# final.net
KiCad netlist of a schematic drawn in EAGLE
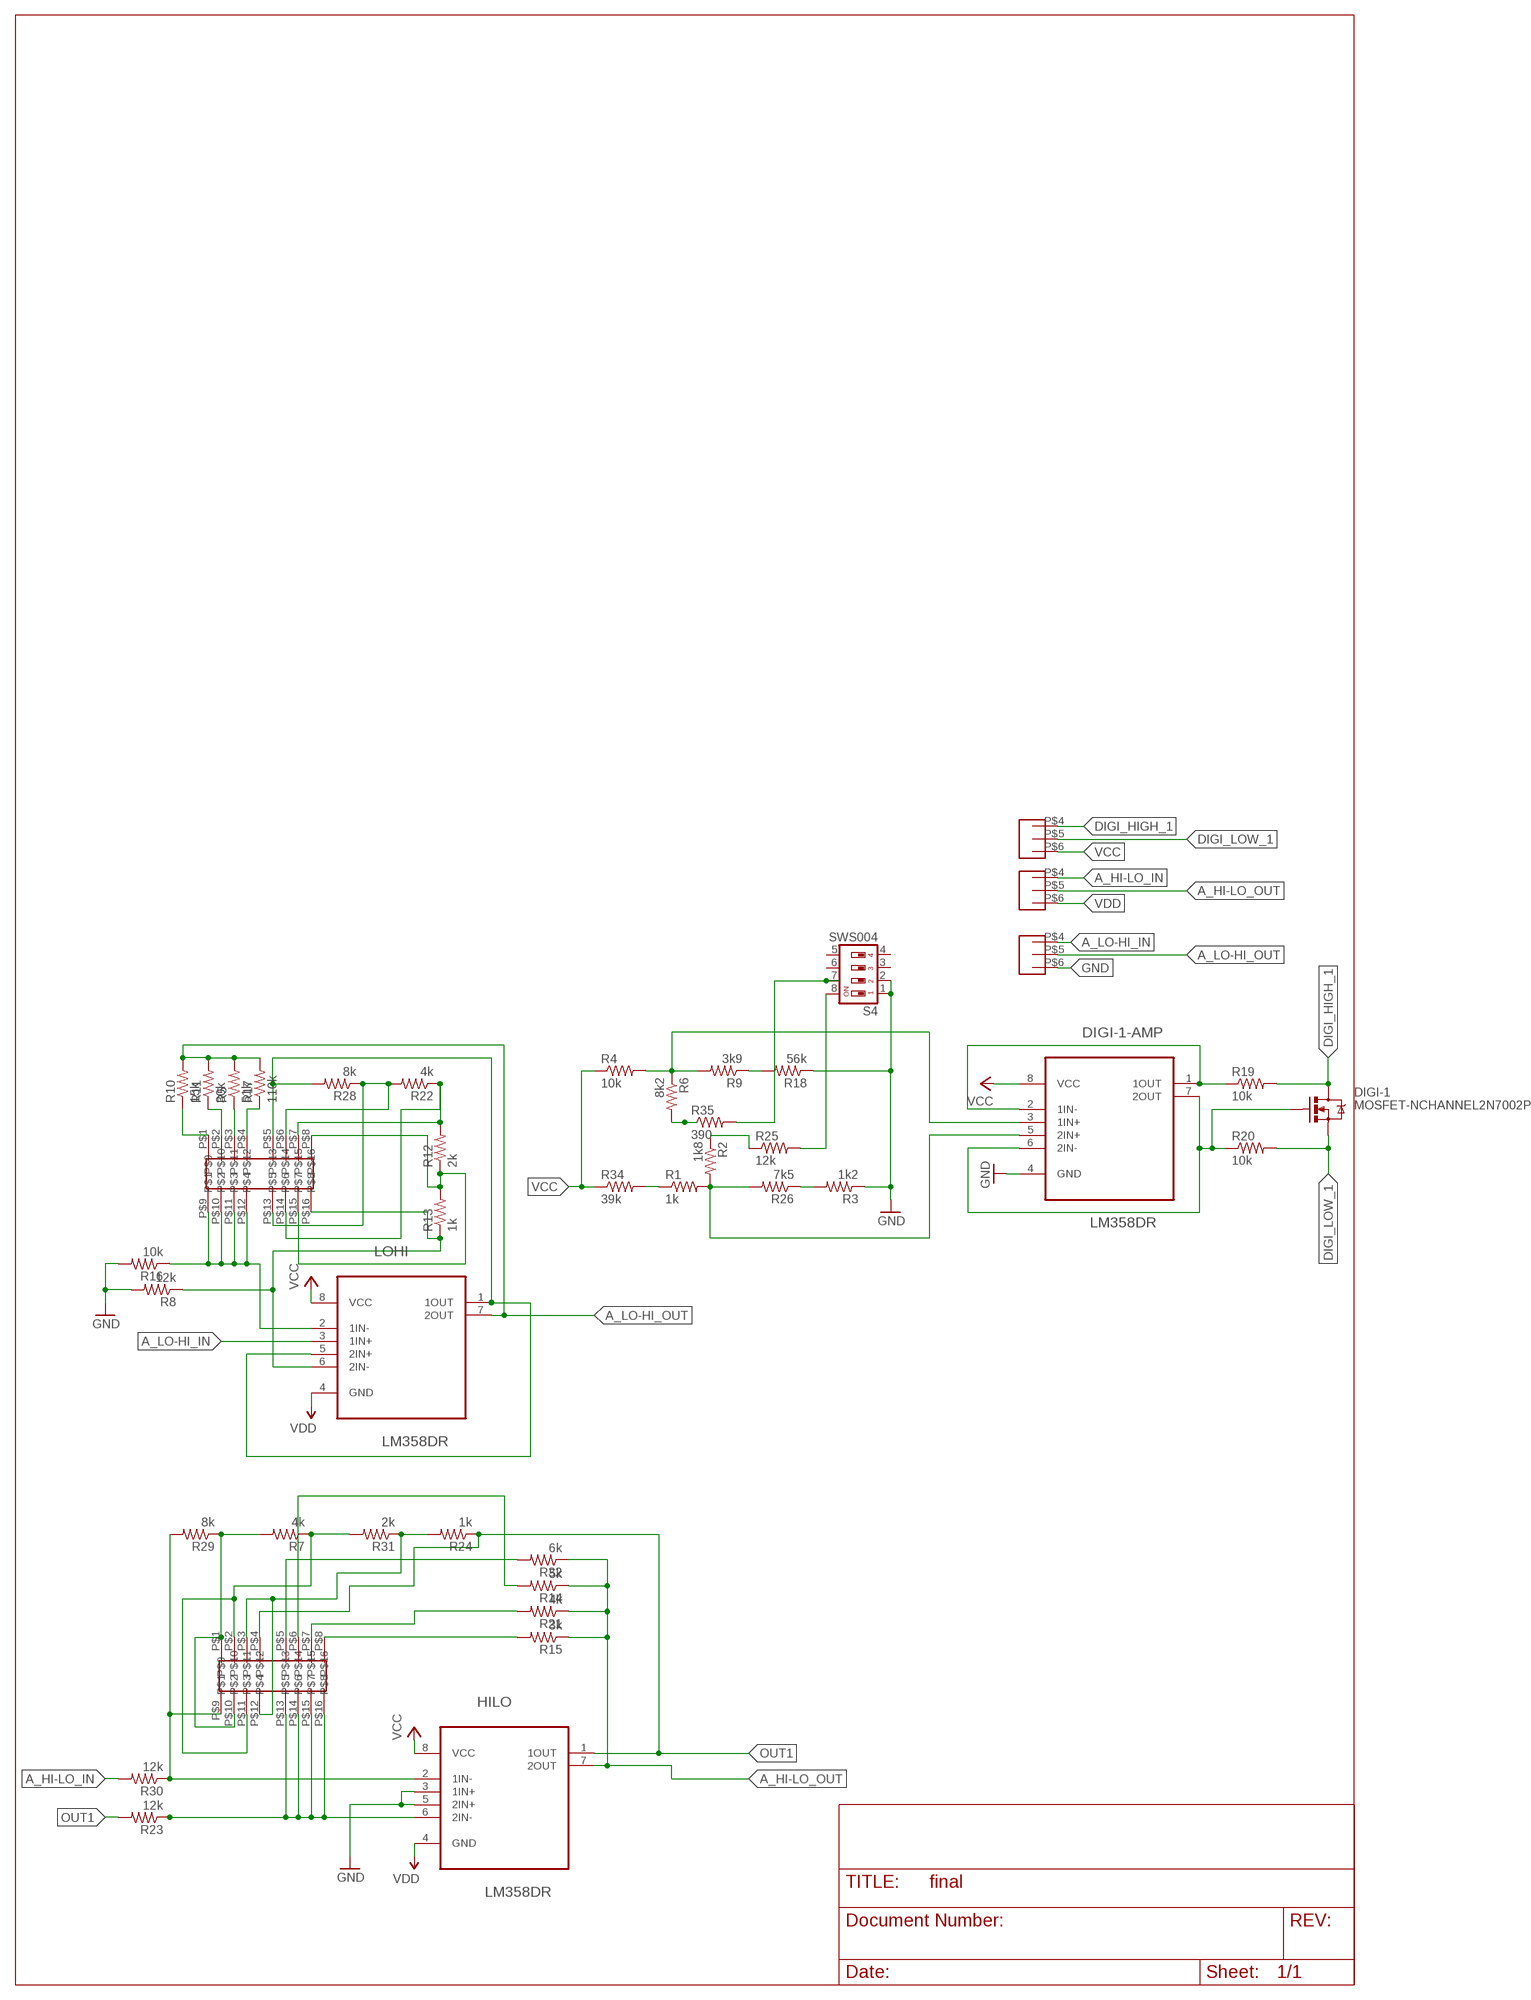
[diagram p0: schematic, sheet 1]

(export (version "E")
  (design (tool "Eeschema 10.0.6"))
  (components
    (comp (ref "DIGI-1")
      (value "MOSFET-NCHANNEL2N7002PW")
      (footprint "eagle-import:SOT323")
      (libsource (lib "eagle-import") (part "MOSFET-NCHANNEL2N7002PW"))
    )
    (comp (ref "DIGI-1-AMP")
      (value "LM358DR")
      (footprint "eagle-import:SOIC127P600X175-8N")
      (libsource (lib "eagle-import") (part "LM358DR"))
    )
    (comp (ref "HILO")
      (value "LM358DR")
      (footprint "eagle-import:SOIC127P600X175-8N")
      (libsource (lib "eagle-import") (part "LM358DR"))
    )
    (comp (ref "LOHI")
      (value "LM358DR")
      (footprint "eagle-import:SOIC127P600X175-8N")
      (libsource (lib "eagle-import") (part "LM358DR"))
    )
    (comp (ref "R1")
      (value "1k")
      (footprint "eagle-import:R0805")
      (libsource (lib "eagle-import") (part "R-US_R0805"))
    )
    (comp (ref "R2")
      (value "1k8")
      (footprint "eagle-import:R0805")
      (libsource (lib "eagle-import") (part "R-US_R0805"))
    )
    (comp (ref "R3")
      (value "1k2")
      (footprint "eagle-import:R0805")
      (libsource (lib "eagle-import") (part "R-US_R0805"))
    )
    (comp (ref "R4")
      (value "10k")
      (footprint "eagle-import:R0805")
      (libsource (lib "eagle-import") (part "R-US_R0805"))
    )
    (comp (ref "R5")
      (value "51k")
      (footprint "eagle-import:R0805")
      (libsource (lib "eagle-import") (part "R-US_R0805"))
    )
    (comp (ref "R6")
      (value "8k2")
      (footprint "eagle-import:R0805")
      (libsource (lib "eagle-import") (part "R-US_R0805"))
    )
    (comp (ref "R7")
      (value "4k")
      (footprint "eagle-import:0207_15")
      (libsource (lib "eagle-import") (part "R-US_0207/15"))
    )
    (comp (ref "R8")
      (value "12k")
      (footprint "eagle-import:R0805")
      (libsource (lib "eagle-import") (part "R-US_R0805"))
    )
    (comp (ref "R9")
      (value "3k9")
      (footprint "eagle-import:R0805")
      (libsource (lib "eagle-import") (part "R-US_R0805"))
    )
    (comp (ref "R10")
      (value "15k")
      (footprint "eagle-import:R0805")
      (libsource (lib "eagle-import") (part "R-US_R0805"))
    )
    (comp (ref "R11")
      (value "30k")
      (footprint "eagle-import:R0805")
      (libsource (lib "eagle-import") (part "R-US_R0805"))
    )
    (comp (ref "R12")
      (value "2k")
      (footprint "eagle-import:0207_15")
      (libsource (lib "eagle-import") (part "R-US_0207/15"))
    )
    (comp (ref "R13")
      (value "1k")
      (footprint "eagle-import:R0805")
      (libsource (lib "eagle-import") (part "R-US_R0805"))
    )
    (comp (ref "R14")
      (value "5k")
      (footprint "eagle-import:R0805")
      (libsource (lib "eagle-import") (part "R-US_R0805"))
    )
    (comp (ref "R15")
      (value "3k")
      (footprint "eagle-import:R0805")
      (libsource (lib "eagle-import") (part "R-US_R0805"))
    )
    (comp (ref "R16")
      (value "10k")
      (footprint "eagle-import:R0805")
      (libsource (lib "eagle-import") (part "R-US_R0805"))
    )
    (comp (ref "R17")
      (value "110k")
      (footprint "eagle-import:R0805")
      (libsource (lib "eagle-import") (part "R-US_R0805"))
    )
    (comp (ref "R18")
      (value "56k")
      (footprint "eagle-import:R0805")
      (libsource (lib "eagle-import") (part "R-US_R0805"))
    )
    (comp (ref "R19")
      (value "10k")
      (footprint "eagle-import:R0805")
      (libsource (lib "eagle-import") (part "R-US_R0805"))
    )
    (comp (ref "R20")
      (value "10k")
      (footprint "eagle-import:R0805")
      (libsource (lib "eagle-import") (part "R-US_R0805"))
    )
    (comp (ref "R21")
      (value "4k")
      (footprint "eagle-import:R0805")
      (libsource (lib "eagle-import") (part "R-US_R0805"))
    )
    (comp (ref "R22")
      (value "4k")
      (footprint "eagle-import:0207_15")
      (libsource (lib "eagle-import") (part "R-US_0207/15"))
    )
    (comp (ref "R23")
      (value "12k")
      (footprint "eagle-import:R0805")
      (libsource (lib "eagle-import") (part "R-US_R0805"))
    )
    (comp (ref "R24")
      (value "1k")
      (footprint "eagle-import:0207_15")
      (libsource (lib "eagle-import") (part "R-US_0207/15"))
    )
    (comp (ref "R25")
      (value "12k")
      (footprint "eagle-import:R0805")
      (libsource (lib "eagle-import") (part "R-US_R0805"))
    )
    (comp (ref "R26")
      (value "7k5")
      (footprint "eagle-import:R0805")
      (libsource (lib "eagle-import") (part "R-US_R0805"))
    )
    (comp (ref "R28")
      (value "8k")
      (footprint "eagle-import:0207_15")
      (libsource (lib "eagle-import") (part "R-US_0207/15"))
    )
    (comp (ref "R29")
      (value "8k")
      (footprint "eagle-import:R0805")
      (libsource (lib "eagle-import") (part "R-US_R0805"))
    )
    (comp (ref "R30")
      (value "12k")
      (footprint "eagle-import:R0805")
      (libsource (lib "eagle-import") (part "R-US_R0805"))
    )
    (comp (ref "R31")
      (value "2k")
      (footprint "eagle-import:0207_15")
      (libsource (lib "eagle-import") (part "R-US_0207/15"))
    )
    (comp (ref "R32")
      (value "6k")
      (footprint "eagle-import:R0805")
      (libsource (lib "eagle-import") (part "R-US_R0805"))
    )
    (comp (ref "R34")
      (value "39k")
      (footprint "eagle-import:R0805")
      (libsource (lib "eagle-import") (part "R-US_R0805"))
    )
    (comp (ref "R35")
      (value "390")
      (footprint "eagle-import:R0805")
      (libsource (lib "eagle-import") (part "R-US_R0805"))
    )
    (comp (ref "S4")
      (value "SWS004")
      (footprint "eagle-import:SMS-004")
      (libsource (lib "eagle-import") (part "SWS004"))
    )
    (comp (ref "U$2")
      (value "USCO_8PIN_SWITCH")
      (footprint "eagle-import:USCO_8PIN_SWITCH")
      (libsource (lib "eagle-import") (part "USCO_8PIN_SWITCH"))
    )
    (comp (ref "U$3")
      (value "USCO_8PIN_SWITCH")
      (footprint "eagle-import:USCO_8PIN_SWITCH")
      (libsource (lib "eagle-import") (part "USCO_8PIN_SWITCH"))
    )
    (comp (ref "U$4")
      (value "5.08PITCHTERMINAL")
      (footprint "eagle-import:10KPL508")
      (libsource (lib "eagle-import") (part "5.08PITCHTERMINAL"))
    )
    (comp (ref "U$5")
      (value "5.08PITCHTERMINAL")
      (footprint "eagle-import:10KPL508")
      (libsource (lib "eagle-import") (part "5.08PITCHTERMINAL"))
    )
    (comp (ref "U$6")
      (value "5.08PITCHTERMINAL")
      (footprint "eagle-import:10KPL508")
      (libsource (lib "eagle-import") (part "5.08PITCHTERMINAL"))
    )
  )
  (nets
    (net (code "1") (name "A_HI-LO_IN") (class "Default")
      (node (ref "R30") (pin "2") (pinfunction "2_2") (pintype "passive"))
      (node (ref "U$4") (pin "P$4") (pinfunction "P$4_P$4") (pintype "bidirectional"))
    )
    (net (code "2") (name "A_HI-LO_OUT") (class "Default")
      (node (ref "HILO") (pin "7") (pinfunction "2OUT_7") (pintype "output"))
      (node (ref "R14") (pin "1") (pinfunction "1_1") (pintype "passive"))
      (node (ref "R15") (pin "1") (pinfunction "1_1") (pintype "passive"))
      (node (ref "R21") (pin "1") (pinfunction "1_1") (pintype "passive"))
      (node (ref "R32") (pin "1") (pinfunction "1_1") (pintype "passive"))
      (node (ref "U$4") (pin "P$5") (pinfunction "P$5_P$5") (pintype "bidirectional"))
    )
    (net (code "3") (name "A_LO-HI_IN") (class "Default")
      (node (ref "LOHI") (pin "3") (pinfunction "1IN+_3") (pintype "input"))
      (node (ref "U$6") (pin "P$4") (pinfunction "P$4_P$4") (pintype "bidirectional"))
    )
    (net (code "4") (name "A_LO-HI_OUT") (class "Default")
      (node (ref "LOHI") (pin "7") (pinfunction "2OUT_7") (pintype "output"))
      (node (ref "R10") (pin "2") (pinfunction "2_2") (pintype "passive"))
      (node (ref "R11") (pin "2") (pinfunction "2_2") (pintype "passive"))
      (node (ref "R17") (pin "2") (pinfunction "2_2") (pintype "passive"))
      (node (ref "R5") (pin "2") (pinfunction "2_2") (pintype "passive"))
      (node (ref "U$6") (pin "P$5") (pinfunction "P$5_P$5") (pintype "bidirectional"))
    )
    (net (code "5") (name "DIGI_HIGH_1") (class "Default")
      (node (ref "DIGI-1") (pin "3") (pinfunction "D_3") (pintype "passive"))
      (node (ref "R19") (pin "2") (pinfunction "2_2") (pintype "passive"))
      (node (ref "U$5") (pin "P$4") (pinfunction "P$4_P$4") (pintype "bidirectional"))
    )
    (net (code "6") (name "DIGI_LOW_1") (class "Default")
      (node (ref "DIGI-1") (pin "2") (pinfunction "S_2") (pintype "passive"))
      (node (ref "R20") (pin "2") (pinfunction "2_2") (pintype "passive"))
      (node (ref "U$5") (pin "P$5") (pinfunction "P$5_P$5") (pintype "bidirectional"))
    )
    (net (code "7") (name "GND") (class "Default")
      (node (ref "DIGI-1-AMP") (pin "4") (pinfunction "GND_4") (pintype "passive"))
      (node (ref "HILO") (pin "3") (pinfunction "1IN+_3") (pintype "input"))
      (node (ref "HILO") (pin "5") (pinfunction "2IN+_5") (pintype "input"))
      (node (ref "R16") (pin "2") (pinfunction "2_2") (pintype "passive"))
      (node (ref "R18") (pin "1") (pinfunction "1_1") (pintype "passive"))
      (node (ref "R3") (pin "1") (pinfunction "1_1") (pintype "passive"))
      (node (ref "R8") (pin "2") (pinfunction "2_2") (pintype "passive"))
      (node (ref "S4") (pin "1") (pinfunction "1_1") (pintype "passive"))
      (node (ref "S4") (pin "2") (pinfunction "2_2") (pintype "passive"))
      (node (ref "U$6") (pin "P$6") (pinfunction "P$6_P$6") (pintype "bidirectional"))
    )
    (net (code "8") (name "Net-(DIGI-1-AMP-1IN+)") (class "Default")
      (node (ref "DIGI-1-AMP") (pin "3") (pinfunction "1IN+_3") (pintype "input"))
      (node (ref "R4") (pin "2") (pinfunction "2_2") (pintype "passive"))
      (node (ref "R6") (pin "1") (pinfunction "1_1") (pintype "passive"))
      (node (ref "R9") (pin "2") (pinfunction "2_2") (pintype "passive"))
    )
    (net (code "9") (name "Net-(DIGI-1-AMP-1IN-)") (class "Default")
      (node (ref "DIGI-1-AMP") (pin "1") (pinfunction "1OUT_1") (pintype "output"))
      (node (ref "DIGI-1-AMP") (pin "2") (pinfunction "1IN-_2") (pintype "input"))
      (node (ref "R19") (pin "1") (pinfunction "1_1") (pintype "passive"))
    )
    (net (code "10") (name "Net-(DIGI-1-AMP-2IN+)") (class "Default")
      (node (ref "DIGI-1-AMP") (pin "5") (pinfunction "2IN+_5") (pintype "input"))
      (node (ref "R1") (pin "2") (pinfunction "2_2") (pintype "passive"))
      (node (ref "R2") (pin "2") (pinfunction "2_2") (pintype "passive"))
      (node (ref "R26") (pin "2") (pinfunction "2_2") (pintype "passive"))
    )
    (net (code "11") (name "Net-(DIGI-1-AMP-2IN-)") (class "Default")
      (node (ref "DIGI-1") (pin "1") (pinfunction "G_1") (pintype "passive"))
      (node (ref "DIGI-1-AMP") (pin "6") (pinfunction "2IN-_6") (pintype "input"))
      (node (ref "DIGI-1-AMP") (pin "7") (pinfunction "2OUT_7") (pintype "output"))
      (node (ref "R20") (pin "1") (pinfunction "1_1") (pintype "passive"))
    )
    (net (code "12") (name "Net-(HILO-1IN-)") (class "Default")
      (node (ref "HILO") (pin "2") (pinfunction "1IN-_2") (pintype "input"))
      (node (ref "R29") (pin "2") (pinfunction "2_2") (pintype "passive"))
      (node (ref "R30") (pin "1") (pinfunction "1_1") (pintype "passive"))
      (node (ref "U$2") (pin "P$9") (pinfunction "P$9_P$9") (pintype "bidirectional"))
    )
    (net (code "13") (name "Net-(HILO-2IN-)") (class "Default")
      (node (ref "HILO") (pin "6") (pinfunction "2IN-_6") (pintype "input"))
      (node (ref "R23") (pin "1") (pinfunction "1_1") (pintype "passive"))
      (node (ref "U$2") (pin "P$13") (pinfunction "P$13_P$13") (pintype "bidirectional"))
      (node (ref "U$2") (pin "P$14") (pinfunction "P$14_P$14") (pintype "bidirectional"))
      (node (ref "U$2") (pin "P$15") (pinfunction "P$15_P$15") (pintype "bidirectional"))
      (node (ref "U$2") (pin "P$16") (pinfunction "P$16_P$16") (pintype "bidirectional"))
    )
    (net (code "14") (name "Net-(LOHI-1IN-)") (class "Default")
      (node (ref "LOHI") (pin "2") (pinfunction "1IN-_2") (pintype "input"))
      (node (ref "R16") (pin "1") (pinfunction "1_1") (pintype "passive"))
      (node (ref "U$3") (pin "P$10") (pinfunction "P$10_P$10") (pintype "bidirectional"))
      (node (ref "U$3") (pin "P$11") (pinfunction "P$11_P$11") (pintype "bidirectional"))
      (node (ref "U$3") (pin "P$12") (pinfunction "P$12_P$12") (pintype "bidirectional"))
      (node (ref "U$3") (pin "P$9") (pinfunction "P$9_P$9") (pintype "bidirectional"))
    )
    (net (code "15") (name "Net-(LOHI-1OUT)") (class "Default")
      (node (ref "LOHI") (pin "1") (pinfunction "1OUT_1") (pintype "output"))
      (node (ref "LOHI") (pin "5") (pinfunction "2IN+_5") (pintype "input"))
      (node (ref "R28") (pin "2") (pinfunction "2_2") (pintype "passive"))
      (node (ref "U$3") (pin "P$5") (pinfunction "P$5_P$5") (pintype "bidirectional"))
    )
    (net (code "16") (name "Net-(LOHI-2IN-)") (class "Default")
      (node (ref "LOHI") (pin "6") (pinfunction "2IN-_6") (pintype "input"))
      (node (ref "R13") (pin "1") (pinfunction "1_1") (pintype "passive"))
      (node (ref "R8") (pin "1") (pinfunction "1_1") (pintype "passive"))
      (node (ref "U$3") (pin "P$16") (pinfunction "P$16_P$16") (pintype "bidirectional"))
    )
    (net (code "17") (name "Net-(R1-Pad1)") (class "Default")
      (node (ref "R1") (pin "1") (pinfunction "1_1") (pintype "passive"))
      (node (ref "R34") (pin "2") (pinfunction "2_2") (pintype "passive"))
    )
    (net (code "18") (name "Net-(R2-Pad1)") (class "Default")
      (node (ref "R2") (pin "1") (pinfunction "1_1") (pintype "passive"))
      (node (ref "R25") (pin "1") (pinfunction "1_1") (pintype "passive"))
    )
    (net (code "19") (name "Net-(R5-Pad1)") (class "Default")
      (node (ref "R5") (pin "1") (pinfunction "1_1") (pintype "passive"))
      (node (ref "U$3") (pin "P$3") (pinfunction "P$3_P$3") (pintype "bidirectional"))
    )
    (net (code "20") (name "Net-(R10-Pad1)") (class "Default")
      (node (ref "R10") (pin "1") (pinfunction "1_1") (pintype "passive"))
      (node (ref "U$3") (pin "P$1") (pinfunction "P$1_P$1") (pintype "bidirectional"))
    )
    (net (code "21") (name "Net-(R11-Pad1)") (class "Default")
      (node (ref "R11") (pin "1") (pinfunction "1_1") (pintype "passive"))
      (node (ref "U$3") (pin "P$2") (pinfunction "P$2_P$2") (pintype "bidirectional"))
    )
    (net (code "22") (name "Net-(R12-Pad1)") (class "Default")
      (node (ref "R12") (pin "1") (pinfunction "1_1") (pintype "passive"))
      (node (ref "R13") (pin "2") (pinfunction "2_2") (pintype "passive"))
      (node (ref "U$3") (pin "P$15") (pinfunction "P$15_P$15") (pintype "bidirectional"))
      (node (ref "U$3") (pin "P$8") (pinfunction "P$8_P$8") (pintype "bidirectional"))
    )
    (net (code "23") (name "Net-(R12-Pad2)") (class "Default")
      (node (ref "R12") (pin "2") (pinfunction "2_2") (pintype "passive"))
      (node (ref "R22") (pin "1") (pinfunction "1_1") (pintype "passive"))
      (node (ref "U$3") (pin "P$14") (pinfunction "P$14_P$14") (pintype "bidirectional"))
      (node (ref "U$3") (pin "P$7") (pinfunction "P$7_P$7") (pintype "bidirectional"))
    )
    (net (code "24") (name "Net-(R14-Pad2)") (class "Default")
      (node (ref "R14") (pin "2") (pinfunction "2_2") (pintype "passive"))
      (node (ref "U$2") (pin "P$6") (pinfunction "P$6_P$6") (pintype "bidirectional"))
    )
    (net (code "25") (name "Net-(R15-Pad2)") (class "Default")
      (node (ref "R15") (pin "2") (pinfunction "2_2") (pintype "passive"))
      (node (ref "U$2") (pin "P$8") (pinfunction "P$8_P$8") (pintype "bidirectional"))
    )
    (net (code "26") (name "Net-(R17-Pad1)") (class "Default")
      (node (ref "R17") (pin "1") (pinfunction "1_1") (pintype "passive"))
      (node (ref "U$3") (pin "P$4") (pinfunction "P$4_P$4") (pintype "bidirectional"))
    )
    (net (code "27") (name "Net-(R18-Pad2)") (class "Default")
      (node (ref "R18") (pin "2") (pinfunction "2_2") (pintype "passive"))
      (node (ref "R9") (pin "1") (pinfunction "1_1") (pintype "passive"))
    )
    (net (code "28") (name "Net-(R21-Pad2)") (class "Default")
      (node (ref "R21") (pin "2") (pinfunction "2_2") (pintype "passive"))
      (node (ref "U$2") (pin "P$7") (pinfunction "P$7_P$7") (pintype "bidirectional"))
    )
    (net (code "29") (name "Net-(R22-Pad2)") (class "Default")
      (node (ref "R22") (pin "2") (pinfunction "2_2") (pintype "passive"))
      (node (ref "R28") (pin "1") (pinfunction "1_1") (pintype "passive"))
      (node (ref "U$3") (pin "P$13") (pinfunction "P$13_P$13") (pintype "bidirectional"))
      (node (ref "U$3") (pin "P$6") (pinfunction "P$6_P$6") (pintype "bidirectional"))
    )
    (net (code "30") (name "Net-(R24-Pad2)") (class "Default")
      (node (ref "R24") (pin "2") (pinfunction "2_2") (pintype "passive"))
      (node (ref "R31") (pin "1") (pinfunction "1_1") (pintype "passive"))
      (node (ref "U$2") (pin "P$12") (pinfunction "P$12_P$12") (pintype "bidirectional"))
      (node (ref "U$2") (pin "P$3") (pinfunction "P$3_P$3") (pintype "bidirectional"))
    )
    (net (code "31") (name "Net-(R25-Pad2)") (class "Default")
      (node (ref "R25") (pin "2") (pinfunction "2_2") (pintype "passive"))
      (node (ref "S4") (pin "8") (pinfunction "8_8") (pintype "passive"))
    )
    (net (code "32") (name "Net-(R26-Pad1)") (class "Default")
      (node (ref "R26") (pin "1") (pinfunction "1_1") (pintype "passive"))
      (node (ref "R3") (pin "2") (pinfunction "2_2") (pintype "passive"))
    )
    (net (code "33") (name "Net-(R29-Pad1)") (class "Default")
      (node (ref "R29") (pin "1") (pinfunction "1_1") (pintype "passive"))
      (node (ref "R7") (pin "2") (pinfunction "2_2") (pintype "passive"))
      (node (ref "U$2") (pin "P$1") (pinfunction "P$1_P$1") (pintype "bidirectional"))
      (node (ref "U$2") (pin "P$10") (pinfunction "P$10_P$10") (pintype "bidirectional"))
    )
    (net (code "34") (name "Net-(R31-Pad2)") (class "Default")
      (node (ref "R31") (pin "2") (pinfunction "2_2") (pintype "passive"))
      (node (ref "R7") (pin "1") (pinfunction "1_1") (pintype "passive"))
      (node (ref "U$2") (pin "P$11") (pinfunction "P$11_P$11") (pintype "bidirectional"))
      (node (ref "U$2") (pin "P$2") (pinfunction "P$2_P$2") (pintype "bidirectional"))
    )
    (net (code "35") (name "Net-(R32-Pad2)") (class "Default")
      (node (ref "R32") (pin "2") (pinfunction "2_2") (pintype "passive"))
      (node (ref "U$2") (pin "P$5") (pinfunction "P$5_P$5") (pintype "bidirectional"))
    )
    (net (code "36") (name "Net-(R35-Pad1)") (class "Default")
      (node (ref "R35") (pin "1") (pinfunction "1_1") (pintype "passive"))
      (node (ref "R6") (pin "2") (pinfunction "2_2") (pintype "passive"))
    )
    (net (code "37") (name "Net-(R35-Pad2)") (class "Default")
      (node (ref "R35") (pin "2") (pinfunction "2_2") (pintype "passive"))
      (node (ref "S4") (pin "7") (pinfunction "7_7") (pintype "passive"))
    )
    (net (code "38") (name "OUT1") (class "Default")
      (node (ref "HILO") (pin "1") (pinfunction "1OUT_1") (pintype "output"))
      (node (ref "R23") (pin "2") (pinfunction "2_2") (pintype "passive"))
      (node (ref "R24") (pin "1") (pinfunction "1_1") (pintype "passive"))
      (node (ref "U$2") (pin "P$4") (pinfunction "P$4_P$4") (pintype "bidirectional"))
    )
    (net (code "39") (name "VCC") (class "Default")
      (node (ref "DIGI-1-AMP") (pin "8") (pinfunction "VCC_8") (pintype "power_in"))
      (node (ref "HILO") (pin "8") (pinfunction "VCC_8") (pintype "power_in"))
      (node (ref "LOHI") (pin "8") (pinfunction "VCC_8") (pintype "power_in"))
      (node (ref "R34") (pin "1") (pinfunction "1_1") (pintype "passive"))
      (node (ref "R4") (pin "1") (pinfunction "1_1") (pintype "passive"))
      (node (ref "U$5") (pin "P$6") (pinfunction "P$6_P$6") (pintype "bidirectional"))
    )
    (net (code "40") (name "VDD") (class "Default")
      (node (ref "HILO") (pin "4") (pinfunction "GND_4") (pintype "passive"))
      (node (ref "LOHI") (pin "4") (pinfunction "GND_4") (pintype "passive"))
      (node (ref "U$4") (pin "P$6") (pinfunction "P$6_P$6") (pintype "bidirectional"))
    )
    (net (code "41") (name "unconnected-(S4-Pad3)") (class "Default")
      (node (ref "S4") (pin "3") (pinfunction "3_3") (pintype "passive"))
    )
    (net (code "42") (name "unconnected-(S4-Pad4)") (class "Default")
      (node (ref "S4") (pin "4") (pinfunction "4_4") (pintype "passive"))
    )
    (net (code "43") (name "unconnected-(S4-Pad5)") (class "Default")
      (node (ref "S4") (pin "5") (pinfunction "5_5") (pintype "passive"))
    )
    (net (code "44") (name "unconnected-(S4-Pad6)") (class "Default")
      (node (ref "S4") (pin "6") (pinfunction "6_6") (pintype "passive"))
    )
  )
)
